# PathFinder.net
KiCad netlist of a schematic drawn in EasyEDA Pro
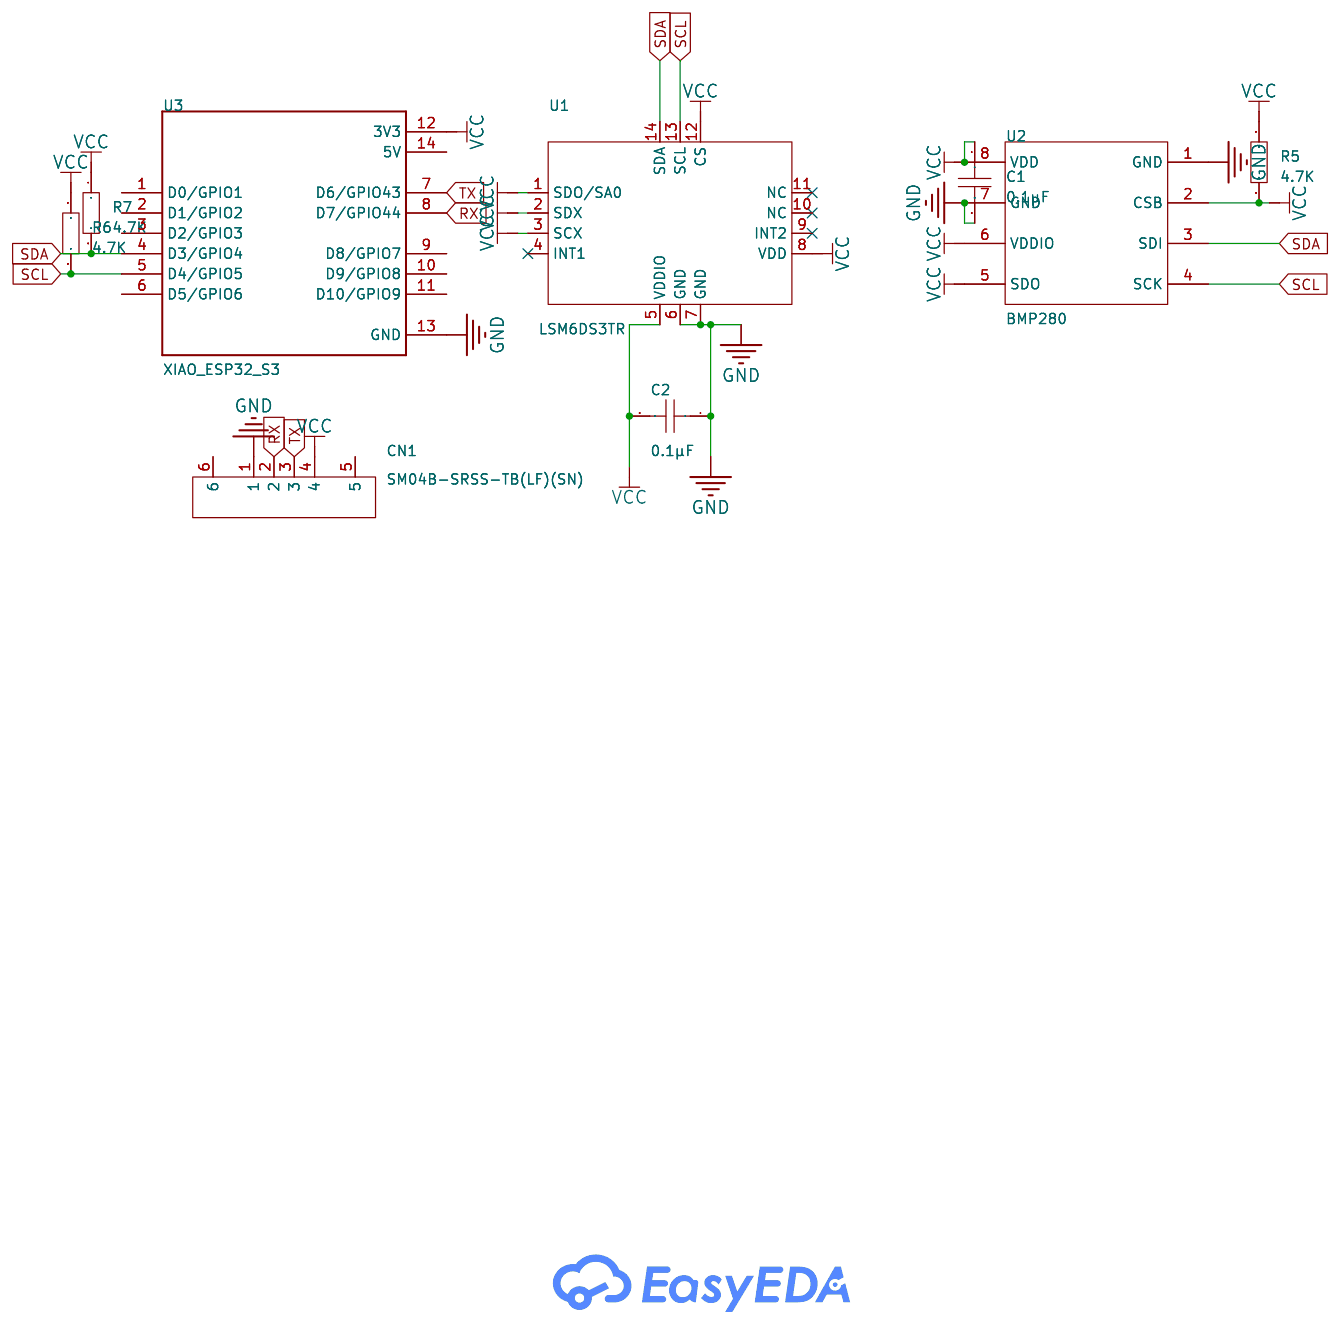
[diagram p0: schematic sheet]

(export (version "E")
  (design (tool "Eeschema 10.0.6"))
  (components
    (comp (ref "C1")
      (value "100nF")
      (footprint "easyedapro:C0603")
      (libsource (lib "easyedapro") (part "CAP"))
    )
    (comp (ref "C2")
      (value "100nF")
      (footprint "easyedapro:C0603")
      (libsource (lib "easyedapro") (part "CAP"))
    )
    (comp (ref "CN1")
      (value "SM04B-SRSS-TB(LF)(SN)")
      (footprint "easyedapro:CONN-SMD_4P-P1.00_SM04B-SRSS-TB-LF-SN")
      (fields (field (name "Manufacturer") "JST"))
      (libsource (lib "easyedapro") (part "SM04B-SRSS-TB (LF)(SN)"))
    )
    (comp (ref "R5") (value "10K") (footprint "easyedapro:R0603") (libsource (lib "easyedapro") (part "Res")))
    (comp (ref "R6") (value "10K") (footprint "easyedapro:R0603") (libsource (lib "easyedapro") (part "Res")))
    (comp (ref "R7") (value "10K") (footprint "easyedapro:R0603") (libsource (lib "easyedapro") (part "Res")))
    (comp (ref "U1")
      (value "LSM6DS3TR")
      (footprint "easyedapro:LGA-14_L3.0-W2.5-P0.50-TL")
      (fields (field (name "Manufacturer") "ST(意法半导体)"))
      (libsource (lib "easyedapro") (part "LSM6DS3TR"))
    )
    (comp (ref "U2")
      (value "BMP280")
      (footprint "easyedapro:LGA-8_L2.5-W2.0-P0.65_AMP6127")
      (fields (field (name "Manufacturer") "Bosch(博世)"))
      (libsource (lib "easyedapro") (part "BMP280"))
    )
    (comp (ref "U3")
      (value "XIAO_ESP32_S3")
      (footprint "easyedapro:MODULE_XIAO_ESP32_S3")
      (libsource (lib "easyedapro") (part "XIAO_ESP32_S3"))
    )
  )
  (nets
    (net (code "1") (name "GND") (class "Default")
      (node (ref "C1") (pin "2") (pinfunction "2_2") (pintype "input"))
      (node (ref "C2") (pin "1") (pinfunction "1_1") (pintype "input"))
      (node (ref "CN1") (pin "1") (pinfunction "1_1") (pintype "unspecified"))
      (node (ref "U1") (pin "6") (pinfunction "GND_6") (pintype "unspecified"))
      (node (ref "U1") (pin "7") (pinfunction "GND_7") (pintype "unspecified"))
      (node (ref "U2") (pin "1") (pinfunction "GND_1") (pintype "unspecified"))
      (node (ref "U2") (pin "7") (pinfunction "GND_7") (pintype "unspecified"))
      (node (ref "U3") (pin "13") (pinfunction "GND_13") (pintype "unspecified"))
    )
    (net (code "2") (name "RX") (class "Default")
      (node (ref "CN1") (pin "2") (pinfunction "2_2") (pintype "unspecified"))
      (node (ref "U3") (pin "8") (pinfunction "D7/GPIO44_8") (pintype "bidirectional"))
    )
    (net (code "3") (name "SCL") (class "Default")
      (node (ref "R6") (pin "2") (pinfunction "2_2") (pintype "input"))
      (node (ref "U1") (pin "13") (pinfunction "SCL_13") (pintype "unspecified"))
      (node (ref "U2") (pin "4") (pinfunction "SCK_4") (pintype "unspecified"))
      (node (ref "U3") (pin "5") (pinfunction "D4/GPIO5_5") (pintype "bidirectional"))
    )
    (net (code "4") (name "SDA") (class "Default")
      (node (ref "R7") (pin "2") (pinfunction "2_2") (pintype "input"))
      (node (ref "U1") (pin "14") (pinfunction "SDA_14") (pintype "unspecified"))
      (node (ref "U2") (pin "3") (pinfunction "SDI_3") (pintype "unspecified"))
      (node (ref "U3") (pin "4") (pinfunction "D3/GPIO4_4") (pintype "bidirectional"))
    )
    (net (code "5") (name "TX") (class "Default")
      (node (ref "CN1") (pin "3") (pinfunction "3_3") (pintype "unspecified"))
      (node (ref "U3") (pin "7") (pinfunction "D6/GPIO43_7") (pintype "bidirectional"))
    )
    (net (code "6") (name "VCC") (class "Default")
      (node (ref "C1") (pin "1") (pinfunction "1_1") (pintype "input"))
      (node (ref "C2") (pin "2") (pinfunction "2_2") (pintype "input"))
      (node (ref "CN1") (pin "4") (pinfunction "4_4") (pintype "unspecified"))
      (node (ref "R5") (pin "1") (pinfunction "1_1") (pintype "input"))
      (node (ref "R5") (pin "2") (pinfunction "2_2") (pintype "input"))
      (node (ref "R6") (pin "1") (pinfunction "1_1") (pintype "input"))
      (node (ref "R7") (pin "1") (pinfunction "1_1") (pintype "input"))
      (node (ref "U1") (pin "1") (pinfunction "SDO/SA0_1") (pintype "unspecified"))
      (node (ref "U1") (pin "12") (pinfunction "CS_12") (pintype "unspecified"))
      (node (ref "U1") (pin "2") (pinfunction "SDX_2") (pintype "unspecified"))
      (node (ref "U1") (pin "3") (pinfunction "SCX_3") (pintype "unspecified"))
      (node (ref "U1") (pin "5") (pinfunction "VDDIO_5") (pintype "unspecified"))
      (node (ref "U1") (pin "8") (pinfunction "VDD_8") (pintype "unspecified"))
      (node (ref "U2") (pin "2") (pinfunction "CSB_2") (pintype "unspecified"))
      (node (ref "U2") (pin "5") (pinfunction "SDO_5") (pintype "unspecified"))
      (node (ref "U2") (pin "6") (pinfunction "VDDIO_6") (pintype "unspecified"))
      (node (ref "U2") (pin "8") (pinfunction "VDD_8") (pintype "unspecified"))
      (node (ref "U3") (pin "12") (pinfunction "3V3_12") (pintype "unspecified"))
    )
    (net (code "7") (name "unconnected-(CN1-Pad5)") (class "Default")
      (node (ref "CN1") (pin "5") (pinfunction "5_5") (pintype "unspecified"))
    )
    (net (code "8") (name "unconnected-(CN1-Pad6)") (class "Default")
      (node (ref "CN1") (pin "6") (pinfunction "6_6") (pintype "unspecified"))
    )
    (net (code "9") (name "unconnected-(U1-INT1-Pad4)") (class "Default")
      (node (ref "U1") (pin "4") (pinfunction "INT1_4") (pintype "unspecified+no_connect"))
    )
    (net (code "10") (name "unconnected-(U1-INT2-Pad9)") (class "Default")
      (node (ref "U1") (pin "9") (pinfunction "INT2_9") (pintype "unspecified+no_connect"))
    )
    (net (code "11") (name "unconnected-(U1-NC-Pad10)") (class "Default")
      (node (ref "U1") (pin "10") (pinfunction "NC_10") (pintype "unspecified+no_connect"))
    )
    (net (code "12") (name "unconnected-(U1-NC-Pad11)") (class "Default")
      (node (ref "U1") (pin "11") (pinfunction "NC_11") (pintype "unspecified+no_connect"))
    )
    (net (code "13") (name "unconnected-(U3-5V-Pad14)") (class "Default")
      (node (ref "U3") (pin "14") (pinfunction "5V_14") (pintype "unspecified"))
    )
    (net (code "14") (name "unconnected-(U3-D0{slash}GPIO1-Pad1)") (class "Default")
      (node (ref "U3") (pin "1") (pinfunction "D0/GPIO1_1") (pintype "bidirectional"))
    )
    (net (code "15") (name "unconnected-(U3-D1{slash}GPIO2-Pad2)") (class "Default")
      (node (ref "U3") (pin "2") (pinfunction "D1/GPIO2_2") (pintype "bidirectional"))
    )
    (net (code "16") (name "unconnected-(U3-D2{slash}GPIO3-Pad3)") (class "Default")
      (node (ref "U3") (pin "3") (pinfunction "D2/GPIO3_3") (pintype "bidirectional"))
    )
    (net (code "17") (name "unconnected-(U3-D5{slash}GPIO6-Pad6)") (class "Default")
      (node (ref "U3") (pin "6") (pinfunction "D5/GPIO6_6") (pintype "bidirectional"))
    )
    (net (code "18") (name "unconnected-(U3-D8{slash}GPIO7-Pad9)") (class "Default")
      (node (ref "U3") (pin "9") (pinfunction "D8/GPIO7_9") (pintype "bidirectional"))
    )
    (net (code "19") (name "unconnected-(U3-D9{slash}GPIO8-Pad10)") (class "Default")
      (node (ref "U3") (pin "10") (pinfunction "D9/GPIO8_10") (pintype "bidirectional"))
    )
    (net (code "20") (name "unconnected-(U3-D10{slash}GPIO9-Pad11)") (class "Default")
      (node (ref "U3") (pin "11") (pinfunction "D10/GPIO9_11") (pintype "bidirectional"))
    )
  )
)
